# STM32F030F4P6.net
KiCad netlist of a schematic drawn in EAGLE
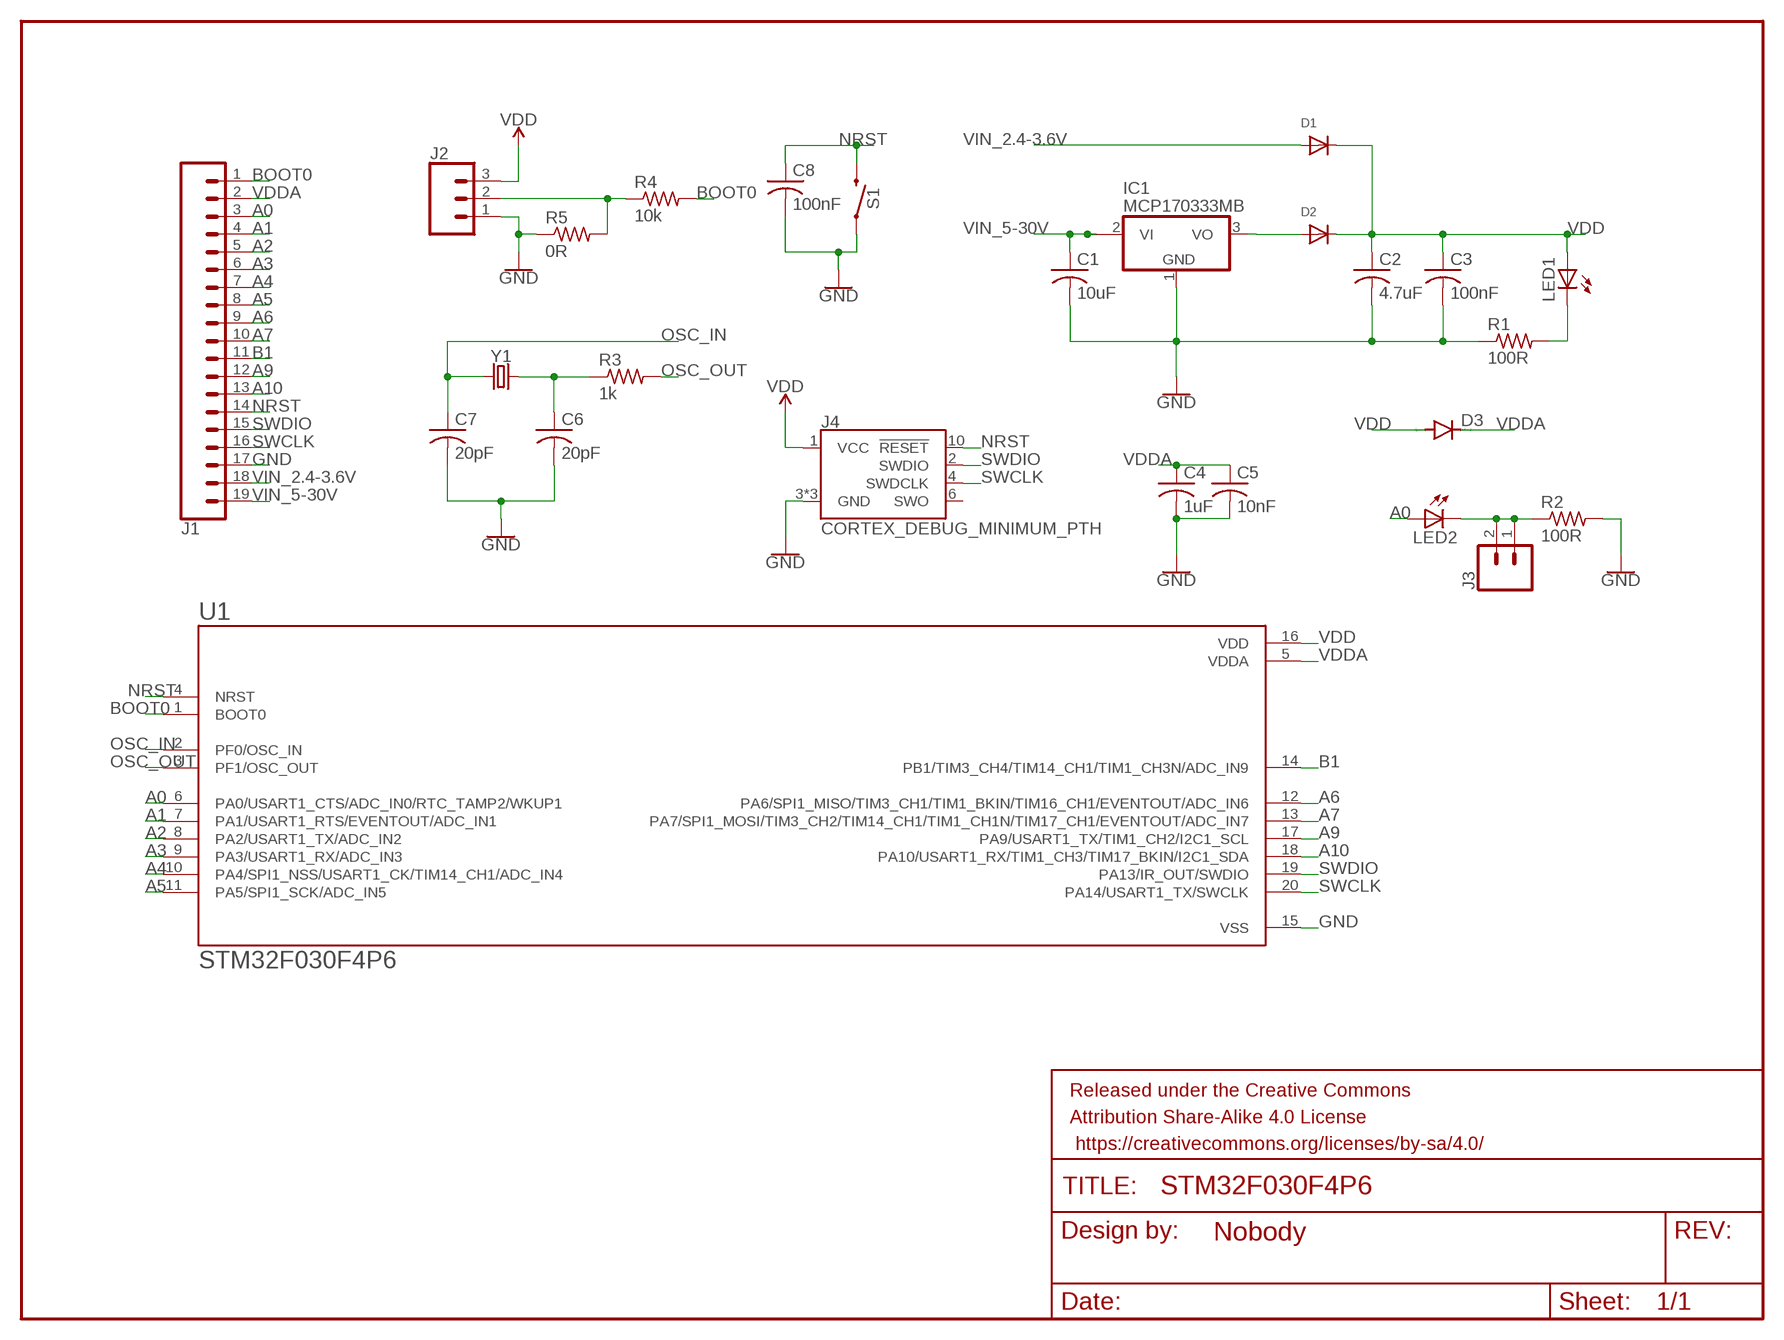
[diagram p0: schematic, sheet 1]

(export (version "E")
  (design (tool "Eeschema 10.0.6"))
  (components
    (comp (ref "C1")
      (value "10uF")
      (footprint "eagle-import:C0603")
      (libsource (lib "eagle-import") (part "C-USC0603"))
    )
    (comp (ref "C2")
      (value "4.7uF")
      (footprint "eagle-import:C0603")
      (libsource (lib "eagle-import") (part "C-USC0603"))
    )
    (comp (ref "C3")
      (value "100nF")
      (footprint "eagle-import:C0603")
      (libsource (lib "eagle-import") (part "C-USC0603"))
    )
    (comp (ref "C4")
      (value "1uF")
      (footprint "eagle-import:C0603")
      (libsource (lib "eagle-import") (part "C-USC0603"))
    )
    (comp (ref "C5")
      (value "10nF")
      (footprint "eagle-import:C0603")
      (libsource (lib "eagle-import") (part "C-USC0603"))
    )
    (comp (ref "C6")
      (value "20pF")
      (footprint "eagle-import:C0603")
      (libsource (lib "eagle-import") (part "C-USC0603"))
    )
    (comp (ref "C7")
      (value "20pF")
      (footprint "eagle-import:C0603")
      (libsource (lib "eagle-import") (part "C-USC0603"))
    )
    (comp (ref "C8")
      (value "100nF")
      (footprint "eagle-import:C0603")
      (libsource (lib "eagle-import") (part "C-USC0603"))
    )
    (comp (ref "D1")
      (value "DIODESOD-123")
      (footprint "eagle-import:SOD-123")
      (libsource (lib "eagle-import") (part "DIODESOD-123"))
    )
    (comp (ref "D2")
      (value "DIODESOD-123")
      (footprint "eagle-import:SOD-123")
      (libsource (lib "eagle-import") (part "DIODESOD-123"))
    )
    (comp (ref "D3")
      (value "DIODE-DO-214AC")
      (footprint "eagle-import:DO-214AC")
      (libsource (lib "eagle-import") (part "DIODE-DO-214AC"))
    )
    (comp (ref "FRAME2")
      (value "FRAME-LETTERNO_PACKAGE")
      (footprint "eagle-import:DUMMY")
      (fields (field (name "DESIGNER") "Nobody"))
      (libsource (lib "eagle-import") (part "FRAME-LETTERNO_PACKAGE"))
    )
    (comp (ref "IC1")
      (value "MCP170333MB")
      (footprint "eagle-import:SOT89")
      (libsource (lib "eagle-import") (part "MCP1703MB33"))
    )
    (comp (ref "J1")
      (value "CONN_19")
      (footprint "eagle-import:1X19")
      (libsource (lib "eagle-import") (part "CONN_19"))
    )
    (comp (ref "J2")
      (value "455-1750-1-ND")
      (footprint "eagle-import:1X03")
      (libsource (lib "eagle-import") (part "CONN_03"))
    )
    (comp (ref "J3")
      (value "CONN_02")
      (footprint "eagle-import:1X02")
      (libsource (lib "eagle-import") (part "CONN_02"))
    )
    (comp (ref "J4")
      (value "CORTEX_DEBUG_MINIMUM_PTH")
      (footprint "eagle-import:2X5-PTH-1.27MM")
      (libsource (lib "eagle-import") (part "CORTEX_DEBUG_MINIMUM_PTH"))
    )
    (comp (ref "LED1")
      (value "LEDCHIPLED_0603")
      (footprint "eagle-import:CHIPLED_0603")
      (libsource (lib "eagle-import") (part "LEDCHIPLED_0603"))
    )
    (comp (ref "LED2")
      (value "LEDCHIPLED_0603")
      (footprint "eagle-import:CHIPLED_0603")
      (libsource (lib "eagle-import") (part "LEDCHIPLED_0603"))
    )
    (comp (ref "R1")
      (value "100R")
      (footprint "eagle-import:R0603")
      (libsource (lib "eagle-import") (part "R-US_R0603"))
    )
    (comp (ref "R2")
      (value "100R")
      (footprint "eagle-import:R0603")
      (libsource (lib "eagle-import") (part "R-US_R0603"))
    )
    (comp (ref "R3")
      (value "1k")
      (footprint "eagle-import:R0603")
      (libsource (lib "eagle-import") (part "R-US_R0603"))
    )
    (comp (ref "R4")
      (value "10k")
      (footprint "eagle-import:R0603")
      (libsource (lib "eagle-import") (part "R-US_R0603"))
    )
    (comp (ref "R5")
      (value "0R")
      (footprint "eagle-import:R0603")
      (libsource (lib "eagle-import") (part "R-US_R0603"))
    )
    (comp (ref "S1")
      (value "MOMENTARY-SWITCH-SPST-SMD-5.2-REDUNDANT")
      (footprint "eagle-import:TACTILE_SWITCH_SMD_5.2MM")
      (libsource (lib "eagle-import") (part "MOMENTARY-SWITCH-SPST-SMD-5.2-REDUNDANT"))
    )
    (comp (ref "U1")
      (value "STM32F030F4P6")
      (footprint "eagle-import:SOP65P640X120-20N")
      (fields (field (name "DIGI-KEY_PART_NUMBER") "497-14044-5-ND") (field (name "MF") "STMicroelectronics"))
      (libsource (lib "eagle-import") (part "STM32F030F4P6"))
    )
    (comp (ref "Y1")
      (value "CRYSTALSMD-5X3.2-2PAD")
      (footprint "eagle-import:CRYSTAL-SMD-5X3.2-2PAD")
      (libsource (lib "eagle-import") (part "CRYSTALSMD-5X3.2-2PAD"))
    )
  )
  (nets
    (net (code "1") (name "/A0") (class "Default")
      (node (ref "J1") (pin "3") (pinfunction "3_3") (pintype "passive"))
      (node (ref "LED2") (pin "A") (pinfunction "A_A") (pintype "passive"))
      (node (ref "U1") (pin "6") (pinfunction "PA0/USART1_CTS/ADC_IN0/RTC_TAMP2/WKUP1_6") (pintype "bidirectional"))
    )
    (net (code "2") (name "/A1") (class "Default")
      (node (ref "J1") (pin "4") (pinfunction "4_4") (pintype "passive"))
      (node (ref "U1") (pin "7") (pinfunction "PA1/USART1_RTS/EVENTOUT/ADC_IN1_7") (pintype "bidirectional"))
    )
    (net (code "3") (name "/A2") (class "Default")
      (node (ref "J1") (pin "5") (pinfunction "5_5") (pintype "passive"))
      (node (ref "U1") (pin "8") (pinfunction "PA2/USART1_TX/ADC_IN2_8") (pintype "bidirectional"))
    )
    (net (code "4") (name "/A3") (class "Default")
      (node (ref "J1") (pin "6") (pinfunction "6_6") (pintype "passive"))
      (node (ref "U1") (pin "9") (pinfunction "PA3/USART1_RX/ADC_IN3_9") (pintype "bidirectional"))
    )
    (net (code "5") (name "/A4") (class "Default")
      (node (ref "J1") (pin "7") (pinfunction "7_7") (pintype "passive"))
      (node (ref "U1") (pin "10") (pinfunction "PA4/SPI1_NSS/USART1_CK/TIM14_CH1/ADC_IN4_10") (pintype "bidirectional"))
    )
    (net (code "6") (name "/A5") (class "Default")
      (node (ref "J1") (pin "8") (pinfunction "8_8") (pintype "passive"))
      (node (ref "U1") (pin "11") (pinfunction "PA5/SPI1_SCK/ADC_IN5_11") (pintype "bidirectional"))
    )
    (net (code "7") (name "/A6") (class "Default")
      (node (ref "J1") (pin "9") (pinfunction "9_9") (pintype "passive"))
      (node (ref "U1") (pin "12") (pinfunction "PA6/SPI1_MISO/TIM3_CH1/TIM1_BKIN/TIM16_CH1/EVENTOUT/ADC_IN6_12") (pintype "bidirectional"))
    )
    (net (code "8") (name "/A7") (class "Default")
      (node (ref "J1") (pin "10") (pinfunction "10_10") (pintype "passive"))
      (node (ref "U1") (pin "13") (pinfunction "PA7/SPI1_MOSI/TIM3_CH2/TIM14_CH1/TIM1_CH1N/TIM17_CH1/EVENTOUT/ADC_IN7_13") (pintype "bidirectional"))
    )
    (net (code "9") (name "/A9") (class "Default")
      (node (ref "J1") (pin "12") (pinfunction "12_12") (pintype "passive"))
      (node (ref "U1") (pin "17") (pinfunction "PA9/USART1_TX/TIM1_CH2/I2C1_SCL_17") (pintype "bidirectional"))
    )
    (net (code "10") (name "/A10") (class "Default")
      (node (ref "J1") (pin "13") (pinfunction "13_13") (pintype "passive"))
      (node (ref "U1") (pin "18") (pinfunction "PA10/USART1_RX/TIM1_CH3/TIM17_BKIN/I2C1_SDA_18") (pintype "bidirectional"))
    )
    (net (code "11") (name "/B1") (class "Default")
      (node (ref "J1") (pin "11") (pinfunction "11_11") (pintype "passive"))
      (node (ref "U1") (pin "14") (pinfunction "PB1/TIM3_CH4/TIM14_CH1/TIM1_CH3N/ADC_IN9_14") (pintype "bidirectional"))
    )
    (net (code "12") (name "/BOOT0") (class "Default")
      (node (ref "J1") (pin "1") (pinfunction "1_1") (pintype "passive"))
      (node (ref "R4") (pin "2") (pinfunction "2_2") (pintype "passive"))
      (node (ref "U1") (pin "1") (pinfunction "BOOT0_1") (pintype "input"))
    )
    (net (code "13") (name "/NRST") (class "Default")
      (node (ref "C8") (pin "1") (pinfunction "1_1") (pintype "passive"))
      (node (ref "J1") (pin "14") (pinfunction "14_14") (pintype "passive"))
      (node (ref "J4") (pin "10") (pinfunction "~{RESET}_10") (pintype "bidirectional"))
      (node (ref "S1") (pin "3") (pinfunction "2_3") (pintype "passive"))
      (node (ref "S1") (pin "4") (pinfunction "2_4") (pintype "passive"))
      (node (ref "U1") (pin "4") (pinfunction "NRST_4") (pintype "bidirectional"))
    )
    (net (code "14") (name "/OSC_IN") (class "Default")
      (node (ref "C7") (pin "1") (pinfunction "1_1") (pintype "passive"))
      (node (ref "U1") (pin "2") (pinfunction "PF0/OSC_IN_2") (pintype "bidirectional"))
      (node (ref "Y1") (pin "P$2") (pinfunction "2_P$2") (pintype "passive"))
    )
    (net (code "15") (name "/OSC_OUT") (class "Default")
      (node (ref "R3") (pin "2") (pinfunction "2_2") (pintype "passive"))
      (node (ref "U1") (pin "3") (pinfunction "PF1/OSC_OUT_3") (pintype "bidirectional"))
    )
    (net (code "16") (name "/SWCLK") (class "Default")
      (node (ref "J1") (pin "16") (pinfunction "16_16") (pintype "passive"))
      (node (ref "J4") (pin "4") (pinfunction "SWDCLK_4") (pintype "bidirectional"))
      (node (ref "U1") (pin "20") (pinfunction "PA14/USART1_TX/SWCLK_20") (pintype "bidirectional"))
    )
    (net (code "17") (name "/SWDIO") (class "Default")
      (node (ref "J1") (pin "15") (pinfunction "15_15") (pintype "passive"))
      (node (ref "J4") (pin "2") (pinfunction "SWDIO_2") (pintype "bidirectional"))
      (node (ref "U1") (pin "19") (pinfunction "PA13/IR_OUT/SWDIO_19") (pintype "bidirectional"))
    )
    (net (code "18") (name "/VDDA") (class "Default")
      (node (ref "C4") (pin "1") (pinfunction "1_1") (pintype "passive"))
      (node (ref "C5") (pin "1") (pinfunction "1_1") (pintype "passive"))
      (node (ref "D3") (pin "C") (pinfunction "C_C") (pintype "passive"))
      (node (ref "J1") (pin "2") (pinfunction "2_2") (pintype "passive"))
      (node (ref "U1") (pin "5") (pinfunction "VDDA_5") (pintype "power_in"))
    )
    (net (code "19") (name "/VIN_2.4-3.6V") (class "Default")
      (node (ref "D1") (pin "A") (pinfunction "A_A") (pintype "passive"))
      (node (ref "J1") (pin "18") (pinfunction "18_18") (pintype "passive"))
    )
    (net (code "20") (name "/VIN_5-30V") (class "Default")
      (node (ref "C1") (pin "1") (pinfunction "1_1") (pintype "passive"))
      (node (ref "IC1") (pin "2@1") (pinfunction "VI1_2@1") (pintype "input"))
      (node (ref "J1") (pin "19") (pinfunction "19_19") (pintype "passive"))
    )
    (net (code "21") (name "GND") (class "Default")
      (node (ref "C1") (pin "2") (pinfunction "2_2") (pintype "passive"))
      (node (ref "C2") (pin "2") (pinfunction "2_2") (pintype "passive"))
      (node (ref "C3") (pin "2") (pinfunction "2_2") (pintype "passive"))
      (node (ref "C4") (pin "2") (pinfunction "2_2") (pintype "passive"))
      (node (ref "C5") (pin "2") (pinfunction "2_2") (pintype "passive"))
      (node (ref "C6") (pin "2") (pinfunction "2_2") (pintype "passive"))
      (node (ref "C7") (pin "2") (pinfunction "2_2") (pintype "passive"))
      (node (ref "C8") (pin "2") (pinfunction "2_2") (pintype "passive"))
      (node (ref "IC1") (pin "1") (pinfunction "GND_1") (pintype "passive"))
      (node (ref "J1") (pin "17") (pinfunction "17_17") (pintype "passive"))
      (node (ref "J2") (pin "1") (pinfunction "1_1") (pintype "passive"))
      (node (ref "J4") (pin "3") (pinfunction "GND_3") (pintype "bidirectional"))
      (node (ref "J4") (pin "5") (pinfunction "GND_5") (pintype "bidirectional"))
      (node (ref "J4") (pin "9") (pinfunction "GND_9") (pintype "bidirectional"))
      (node (ref "R1") (pin "1") (pinfunction "1_1") (pintype "passive"))
      (node (ref "R2") (pin "2") (pinfunction "2_2") (pintype "passive"))
      (node (ref "R5") (pin "1") (pinfunction "1_1") (pintype "passive"))
      (node (ref "S1") (pin "1") (pinfunction "1_1") (pintype "passive"))
      (node (ref "S1") (pin "2") (pinfunction "1_2") (pintype "passive"))
      (node (ref "U1") (pin "15") (pinfunction "VSS_15") (pintype "power_in"))
    )
    (net (code "22") (name "Net-(IC1-VO)") (class "Default")
      (node (ref "D2") (pin "A") (pinfunction "A_A") (pintype "passive"))
      (node (ref "IC1") (pin "3") (pinfunction "VO_3") (pintype "passive"))
    )
    (net (code "23") (name "Net-(J2-Pad2)") (class "Default")
      (node (ref "J2") (pin "2") (pinfunction "2_2") (pintype "passive"))
      (node (ref "R4") (pin "1") (pinfunction "1_1") (pintype "passive"))
      (node (ref "R5") (pin "2") (pinfunction "2_2") (pintype "passive"))
    )
    (net (code "24") (name "Net-(J3-Pad1)") (class "Default")
      (node (ref "J3") (pin "1") (pinfunction "1_1") (pintype "passive"))
      (node (ref "J3") (pin "2") (pinfunction "2_2") (pintype "passive"))
      (node (ref "LED2") (pin "C") (pinfunction "C_C") (pintype "passive"))
      (node (ref "R2") (pin "1") (pinfunction "1_1") (pintype "passive"))
    )
    (net (code "25") (name "Net-(LED1-PadC)") (class "Default")
      (node (ref "LED1") (pin "C") (pinfunction "C_C") (pintype "passive"))
      (node (ref "R1") (pin "2") (pinfunction "2_2") (pintype "passive"))
    )
    (net (code "26") (name "Net-(Y1-1)") (class "Default")
      (node (ref "C6") (pin "1") (pinfunction "1_1") (pintype "passive"))
      (node (ref "R3") (pin "1") (pinfunction "1_1") (pintype "passive"))
      (node (ref "Y1") (pin "P$1") (pinfunction "1_P$1") (pintype "passive"))
    )
    (net (code "27") (name "VDD") (class "Default")
      (node (ref "C2") (pin "1") (pinfunction "1_1") (pintype "passive"))
      (node (ref "C3") (pin "1") (pinfunction "1_1") (pintype "passive"))
      (node (ref "D1") (pin "C") (pinfunction "C_C") (pintype "passive"))
      (node (ref "D2") (pin "C") (pinfunction "C_C") (pintype "passive"))
      (node (ref "D3") (pin "A") (pinfunction "A_A") (pintype "passive"))
      (node (ref "J2") (pin "3") (pinfunction "3_3") (pintype "passive"))
      (node (ref "J4") (pin "1") (pinfunction "VCC_1") (pintype "bidirectional"))
      (node (ref "LED1") (pin "A") (pinfunction "A_A") (pintype "passive"))
      (node (ref "U1") (pin "16") (pinfunction "VDD_16") (pintype "power_in"))
    )
    (net (code "28") (name "unconnected-(IC1-VI-Pad2)") (class "Default")
      (node (ref "IC1") (pin "2") (pinfunction "VI_2") (pintype "input"))
    )
    (net (code "29") (name "unconnected-(J4-SWO-Pad6)") (class "Default")
      (node (ref "J4") (pin "6") (pinfunction "SWO_6") (pintype "bidirectional"))
    )
  )
)
